# BLDC_Motor.net
KiCad netlist of a schematic drawn in EAGLE
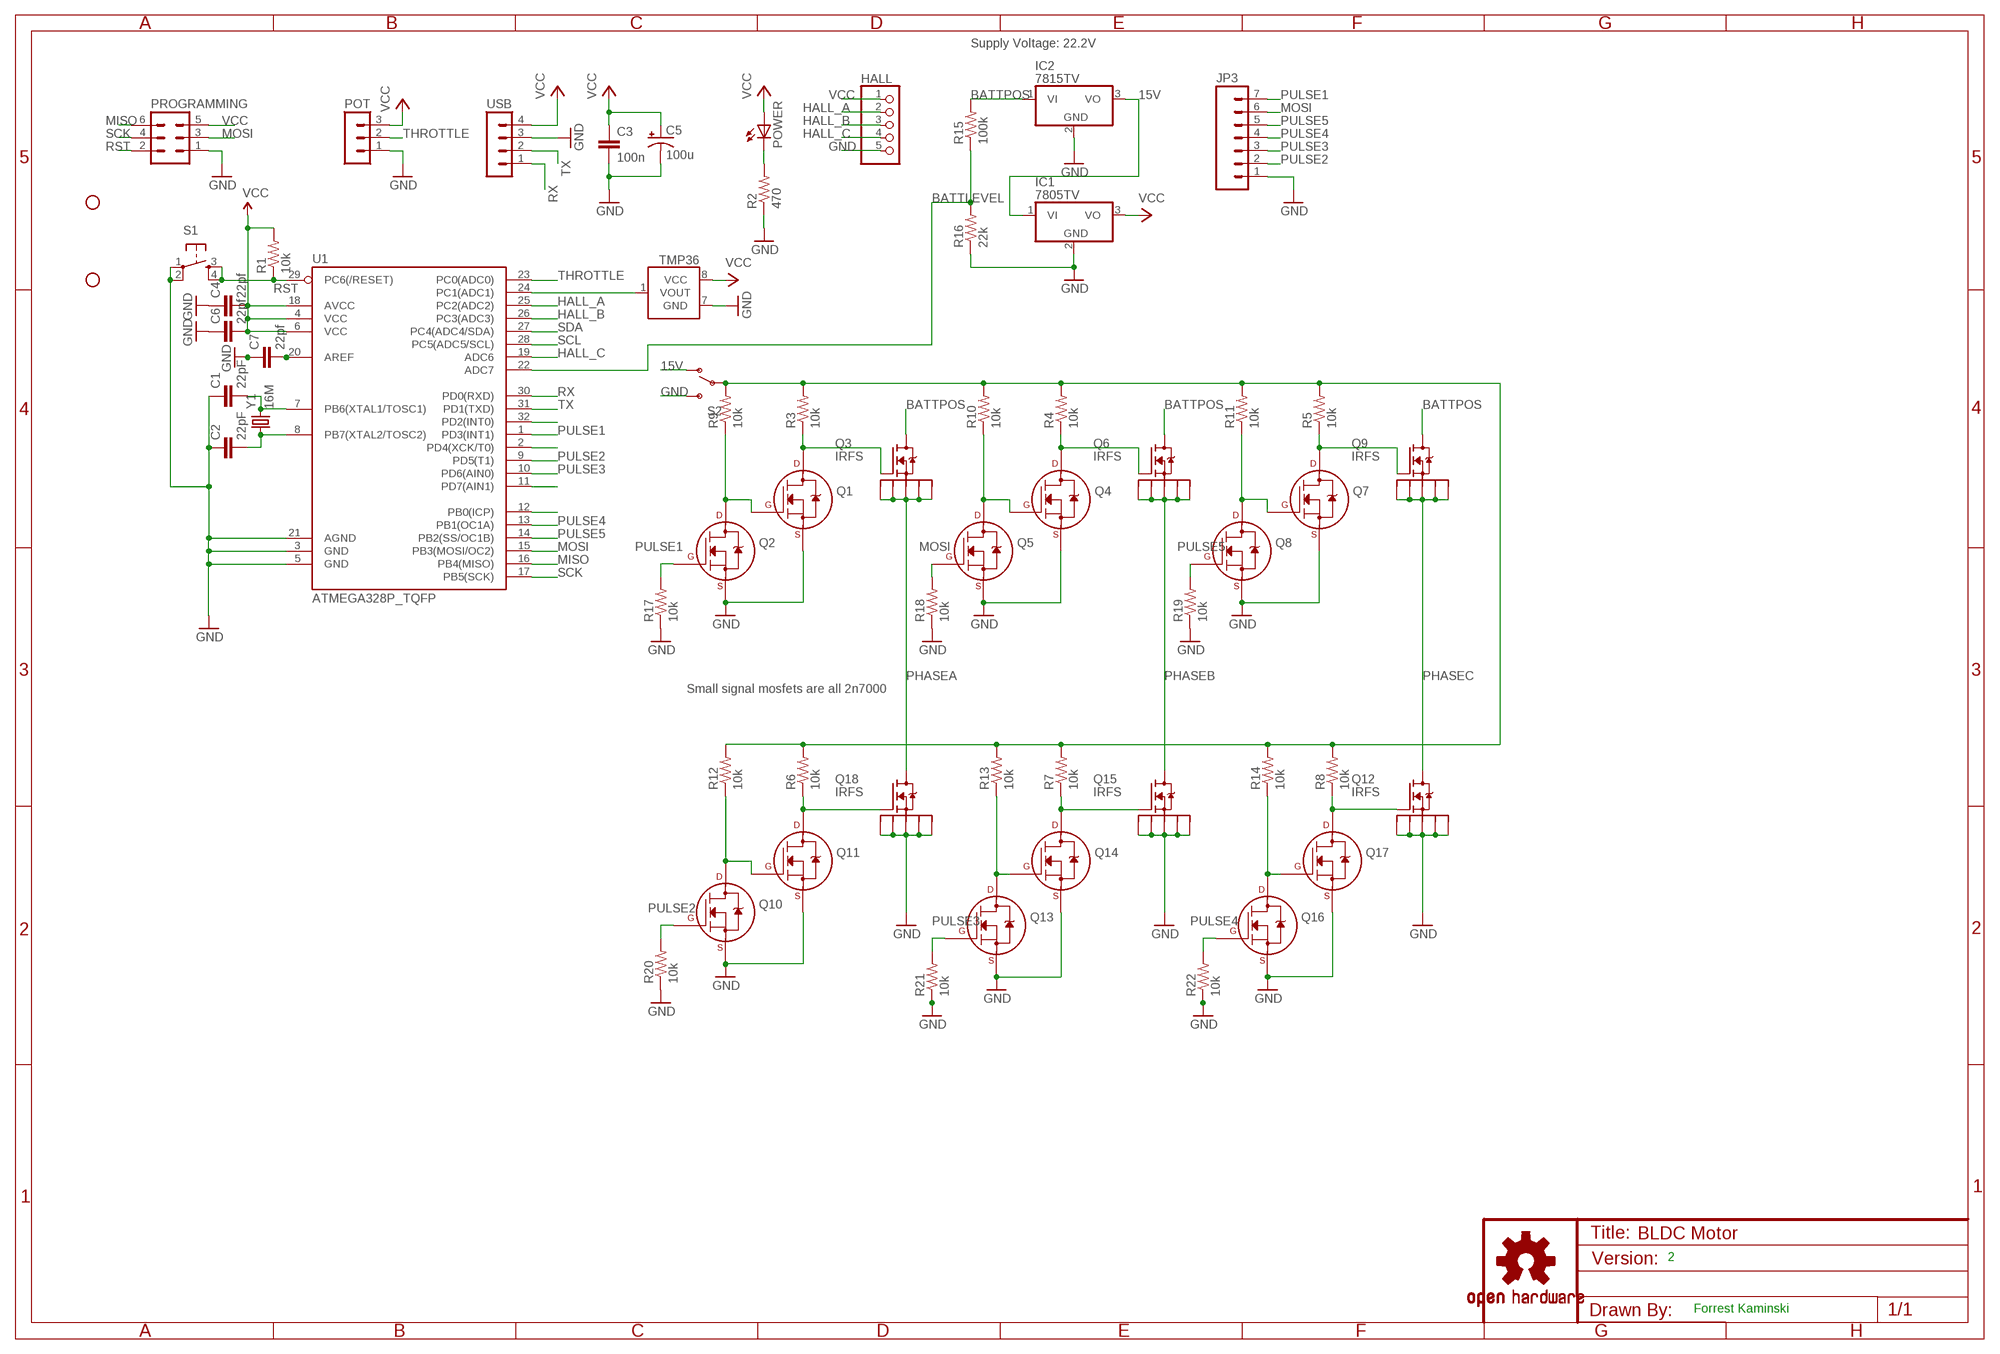
[diagram p0: schematic, sheet 1]

(export (version "E")
  (design (tool "Eeschema 10.0.6"))
  (components
    (comp (ref "C1")
      (value "22pF")
      (footprint "eagle-import:0805")
      (libsource (lib "eagle-import") (part "CAP0805"))
    )
    (comp (ref "C2")
      (value "22pF")
      (footprint "eagle-import:0805")
      (libsource (lib "eagle-import") (part "CAP0805"))
    )
    (comp (ref "C3")
      (value "100n")
      (footprint "eagle-import:0805")
      (libsource (lib "eagle-import") (part "CAP0805"))
    )
    (comp (ref "C4")
      (value "22pf")
      (footprint "eagle-import:0805")
      (libsource (lib "eagle-import") (part "CAP0805"))
    )
    (comp (ref "C5")
      (value "100u")
      (footprint "eagle-import:CPOL-RADIAL-100UF-25V")
      (libsource (lib "eagle-import") (part "CAP_POLPTH1"))
    )
    (comp (ref "C6")
      (value "22pf")
      (footprint "eagle-import:0805")
      (libsource (lib "eagle-import") (part "CAP0805"))
    )
    (comp (ref "C7")
      (value "22pf")
      (footprint "eagle-import:0805")
      (libsource (lib "eagle-import") (part "CAP0805"))
    )
    (comp (ref "HALL")
      (value "PINHD-1X5")
      (footprint "eagle-import:1X05")
      (libsource (lib "eagle-import") (part "PINHD-1X5"))
    )
    (comp (ref "IC1")
      (value "7805TV")
      (footprint "eagle-import:TO220V")
      (libsource (lib "eagle-import") (part "78TV05"))
    )
    (comp (ref "IC2")
      (value "7815TV")
      (footprint "eagle-import:TO220V")
      (libsource (lib "eagle-import") (part "78TV15"))
    )
    (comp (ref "JP1")
      (value "STAND-OFF")
      (footprint "eagle-import:STAND-OFF")
      (libsource (lib "eagle-import") (part "STAND-OFF"))
    )
    (comp (ref "JP2")
      (value "STAND-OFF")
      (footprint "eagle-import:STAND-OFF")
      (libsource (lib "eagle-import") (part "STAND-OFF"))
    )
    (comp (ref "JP3")
      (value "M07")
      (footprint "eagle-import:1X07")
      (libsource (lib "eagle-import") (part "M07"))
    )
    (comp (ref "POT")
      (value "MA03-1")
      (footprint "eagle-import:MA03-1")
      (libsource (lib "eagle-import") (part "MA03-1"))
    )
    (comp (ref "POWER")
      (value "LEDSML0805")
      (footprint "eagle-import:SML0805")
      (libsource (lib "eagle-import") (part "LEDSML0805"))
    )
    (comp (ref "PROGRAMMING")
      (value "MA03-2")
      (footprint "eagle-import:MA03-2")
      (libsource (lib "eagle-import") (part "MA03-2"))
    )
    (comp (ref "Q1")
      (value "2N7000_TO92")
      (footprint "eagle-import:TO-92")
      (libsource (lib "eagle-import") (part "2N700_TO920"))
    )
    (comp (ref "Q2")
      (value "2N7000_TO92")
      (footprint "eagle-import:TO-92")
      (libsource (lib "eagle-import") (part "2N700_TO920"))
    )
    (comp (ref "Q3")
      (value "IRFS")
      (footprint "eagle-import:D2PAK-7")
      (libsource (lib "eagle-import") (part "NMOSFET-D2PAK-7"))
    )
    (comp (ref "Q4")
      (value "2N7000_TO92")
      (footprint "eagle-import:TO-92")
      (libsource (lib "eagle-import") (part "2N700_TO920"))
    )
    (comp (ref "Q5")
      (value "2N7000_TO92")
      (footprint "eagle-import:TO-92")
      (libsource (lib "eagle-import") (part "2N700_TO920"))
    )
    (comp (ref "Q6")
      (value "IRFS")
      (footprint "eagle-import:D2PAK-7")
      (libsource (lib "eagle-import") (part "NMOSFET-D2PAK-7"))
    )
    (comp (ref "Q7")
      (value "2N7000_TO92")
      (footprint "eagle-import:TO-92")
      (libsource (lib "eagle-import") (part "2N700_TO920"))
    )
    (comp (ref "Q8")
      (value "2N7000_TO92")
      (footprint "eagle-import:TO-92")
      (libsource (lib "eagle-import") (part "2N700_TO920"))
    )
    (comp (ref "Q9")
      (value "IRFS")
      (footprint "eagle-import:D2PAK-7")
      (libsource (lib "eagle-import") (part "NMOSFET-D2PAK-7"))
    )
    (comp (ref "Q10")
      (value "2N7000_TO92")
      (footprint "eagle-import:TO-92")
      (libsource (lib "eagle-import") (part "2N700_TO920"))
    )
    (comp (ref "Q11")
      (value "2N7000_TO92")
      (footprint "eagle-import:TO-92")
      (libsource (lib "eagle-import") (part "2N700_TO920"))
    )
    (comp (ref "Q12")
      (value "IRFS")
      (footprint "eagle-import:D2PAK-7")
      (libsource (lib "eagle-import") (part "NMOSFET-D2PAK-7"))
    )
    (comp (ref "Q13")
      (value "2N7000_TO92")
      (footprint "eagle-import:TO-92")
      (libsource (lib "eagle-import") (part "2N700_TO920"))
    )
    (comp (ref "Q14")
      (value "2N7000_TO92")
      (footprint "eagle-import:TO-92")
      (libsource (lib "eagle-import") (part "2N700_TO920"))
    )
    (comp (ref "Q15")
      (value "IRFS")
      (footprint "eagle-import:D2PAK-7")
      (libsource (lib "eagle-import") (part "NMOSFET-D2PAK-7"))
    )
    (comp (ref "Q16")
      (value "2N7000_TO92")
      (footprint "eagle-import:TO-92")
      (libsource (lib "eagle-import") (part "2N700_TO920"))
    )
    (comp (ref "Q17")
      (value "2N7000_TO92")
      (footprint "eagle-import:TO-92")
      (libsource (lib "eagle-import") (part "2N700_TO920"))
    )
    (comp (ref "Q18")
      (value "IRFS")
      (footprint "eagle-import:D2PAK-7")
      (libsource (lib "eagle-import") (part "NMOSFET-D2PAK-7"))
    )
    (comp (ref "R1")
      (value "10k")
      (footprint "eagle-import:0805")
      (libsource (lib "eagle-import") (part "RESISTOR0805-RES"))
    )
    (comp (ref "R2")
      (value "470")
      (footprint "eagle-import:0805")
      (libsource (lib "eagle-import") (part "RESISTOR0805-RES"))
    )
    (comp (ref "R3")
      (value "10k")
      (footprint "eagle-import:0805")
      (libsource (lib "eagle-import") (part "RESISTOR0805-RES"))
    )
    (comp (ref "R4")
      (value "10k")
      (footprint "eagle-import:0805")
      (libsource (lib "eagle-import") (part "RESISTOR0805-RES"))
    )
    (comp (ref "R5")
      (value "10k")
      (footprint "eagle-import:0805")
      (libsource (lib "eagle-import") (part "RESISTOR0805-RES"))
    )
    (comp (ref "R6")
      (value "10k")
      (footprint "eagle-import:0805")
      (libsource (lib "eagle-import") (part "RESISTOR0805-RES"))
    )
    (comp (ref "R7")
      (value "10k")
      (footprint "eagle-import:0805")
      (libsource (lib "eagle-import") (part "RESISTOR0805-RES"))
    )
    (comp (ref "R8")
      (value "10k")
      (footprint "eagle-import:0805")
      (libsource (lib "eagle-import") (part "RESISTOR0805-RES"))
    )
    (comp (ref "R9")
      (value "10k")
      (footprint "eagle-import:0805")
      (libsource (lib "eagle-import") (part "RESISTOR0805-RES"))
    )
    (comp (ref "R10")
      (value "10k")
      (footprint "eagle-import:0805")
      (libsource (lib "eagle-import") (part "RESISTOR0805-RES"))
    )
    (comp (ref "R11")
      (value "10k")
      (footprint "eagle-import:0805")
      (libsource (lib "eagle-import") (part "RESISTOR0805-RES"))
    )
    (comp (ref "R12")
      (value "10k")
      (footprint "eagle-import:0805")
      (libsource (lib "eagle-import") (part "RESISTOR0805-RES"))
    )
    (comp (ref "R13")
      (value "10k")
      (footprint "eagle-import:0805")
      (libsource (lib "eagle-import") (part "RESISTOR0805-RES"))
    )
    (comp (ref "R14")
      (value "10k")
      (footprint "eagle-import:0805")
      (libsource (lib "eagle-import") (part "RESISTOR0805-RES"))
    )
    (comp (ref "R15")
      (value "100k")
      (footprint "eagle-import:0805")
      (libsource (lib "eagle-import") (part "RESISTOR0805-RES"))
    )
    (comp (ref "R16")
      (value "22k")
      (footprint "eagle-import:0805")
      (libsource (lib "eagle-import") (part "RESISTOR0805-RES"))
    )
    (comp (ref "R17")
      (value "10k")
      (footprint "eagle-import:0805")
      (libsource (lib "eagle-import") (part "RESISTOR0805-RES"))
    )
    (comp (ref "R18")
      (value "10k")
      (footprint "eagle-import:0805")
      (libsource (lib "eagle-import") (part "RESISTOR0805-RES"))
    )
    (comp (ref "R19")
      (value "10k")
      (footprint "eagle-import:0805")
      (libsource (lib "eagle-import") (part "RESISTOR0805-RES"))
    )
    (comp (ref "R20")
      (value "10k")
      (footprint "eagle-import:0805")
      (libsource (lib "eagle-import") (part "RESISTOR0805-RES"))
    )
    (comp (ref "R21")
      (value "10k")
      (footprint "eagle-import:0805")
      (libsource (lib "eagle-import") (part "RESISTOR0805-RES"))
    )
    (comp (ref "R22")
      (value "10k")
      (footprint "eagle-import:0805")
      (libsource (lib "eagle-import") (part "RESISTOR0805-RES"))
    )
    (comp (ref "S1")
      (value "TAC_SWITCHPTH")
      (footprint "eagle-import:TACTILE-PTH")
      (libsource (lib "eagle-import") (part "TAC_SWITCHPTH"))
    )
    (comp (ref "S2")
      (value "SWITCH-SPSTPTH_LOCK")
      (footprint "eagle-import:SWITCH-SPDT_LOCK.007S")
      (libsource (lib "eagle-import") (part "SWITCH-SPSTPTH_LOCK"))
    )
    (comp (ref "TMP36")
      (value "TMP36SOIC")
      (footprint "eagle-import:SOIC8")
      (libsource (lib "eagle-import") (part "TMP36SOIC"))
    )
    (comp (ref "U$1")
      (value "OSHW-LOGOS")
      (footprint "eagle-import:OSHW-LOGO-S")
      (libsource (lib "eagle-import") (part "OSHW-LOGOS"))
    )
    (comp (ref "U1")
      (value "ATMEGA328P_TQFP")
      (footprint "eagle-import:TQFP32-08")
      (libsource (lib "eagle-import") (part "ATMEGA328P_TQFP"))
    )
    (comp (ref "USB")
      (value "MA04-1")
      (footprint "eagle-import:MA04-1")
      (libsource (lib "eagle-import") (part "MA04-1"))
    )
    (comp (ref "Y1")
      (value "16M")
      (footprint "eagle-import:HC49US")
      (libsource (lib "eagle-import") (part "CRYSTALHC49US"))
    )
  )
  (nets
    (net (code "1") (name "/15V") (class "Default")
      (node (ref "IC1") (pin "1") (pinfunction "VI_1") (pintype "input"))
      (node (ref "IC2") (pin "3") (pinfunction "VO_3") (pintype "passive"))
      (node (ref "S2") (pin "1") (pinfunction "O_1") (pintype "passive"))
    )
    (net (code "2") (name "/BATTLEVEL") (class "Default")
      (node (ref "R15") (pin "1") (pinfunction "1_1") (pintype "passive"))
      (node (ref "R16") (pin "2") (pinfunction "2_2") (pintype "passive"))
      (node (ref "U1") (pin "22") (pinfunction "ADC7_22") (pintype "bidirectional"))
    )
    (net (code "3") (name "/BATTPOS") (class "Default")
      (node (ref "IC2") (pin "1") (pinfunction "VI_1") (pintype "input"))
      (node (ref "Q3") (pin "D") (pinfunction "D_D") (pintype "passive"))
      (node (ref "Q6") (pin "D") (pinfunction "D_D") (pintype "passive"))
      (node (ref "Q9") (pin "D") (pinfunction "D_D") (pintype "passive"))
      (node (ref "R15") (pin "2") (pinfunction "2_2") (pintype "passive"))
    )
    (net (code "4") (name "/HALL_A") (class "Default")
      (node (ref "HALL") (pin "2") (pinfunction "2_2") (pintype "passive"))
      (node (ref "U1") (pin "25") (pinfunction "PC2(ADC2)_25") (pintype "bidirectional"))
    )
    (net (code "5") (name "/HALL_B") (class "Default")
      (node (ref "HALL") (pin "3") (pinfunction "3_3") (pintype "passive"))
      (node (ref "U1") (pin "26") (pinfunction "PC3(ADC3)_26") (pintype "bidirectional"))
    )
    (net (code "6") (name "/HALL_C") (class "Default")
      (node (ref "HALL") (pin "4") (pinfunction "4_4") (pintype "passive"))
      (node (ref "U1") (pin "19") (pinfunction "ADC6_19") (pintype "bidirectional"))
    )
    (net (code "7") (name "/MISO") (class "Default")
      (node (ref "PROGRAMMING") (pin "6") (pinfunction "6_6") (pintype "passive"))
      (node (ref "U1") (pin "16") (pinfunction "PB4(MISO)_16") (pintype "bidirectional"))
    )
    (net (code "8") (name "/MOSI") (class "Default")
      (node (ref "JP3") (pin "6") (pinfunction "6_6") (pintype "passive"))
      (node (ref "PROGRAMMING") (pin "3") (pinfunction "3_3") (pintype "passive"))
      (node (ref "Q5") (pin "2") (pinfunction "G_2") (pintype "tri_state"))
      (node (ref "R18") (pin "2") (pinfunction "2_2") (pintype "passive"))
      (node (ref "U1") (pin "15") (pinfunction "PB3(MOSI/OC2)_15") (pintype "bidirectional"))
    )
    (net (code "9") (name "/PHASEA") (class "Default")
      (node (ref "Q18") (pin "D") (pinfunction "D_D") (pintype "passive"))
      (node (ref "Q3") (pin "S1") (pinfunction "S1_S1") (pintype "passive"))
      (node (ref "Q3") (pin "S2") (pinfunction "S2_S2") (pintype "passive"))
      (node (ref "Q3") (pin "S3") (pinfunction "S3_S3") (pintype "passive"))
      (node (ref "Q3") (pin "S4") (pinfunction "S4_S4") (pintype "passive"))
      (node (ref "Q3") (pin "S5") (pinfunction "S5_S5") (pintype "passive"))
    )
    (net (code "10") (name "/PHASEB") (class "Default")
      (node (ref "Q15") (pin "D") (pinfunction "D_D") (pintype "passive"))
      (node (ref "Q6") (pin "S1") (pinfunction "S1_S1") (pintype "passive"))
      (node (ref "Q6") (pin "S2") (pinfunction "S2_S2") (pintype "passive"))
      (node (ref "Q6") (pin "S3") (pinfunction "S3_S3") (pintype "passive"))
      (node (ref "Q6") (pin "S4") (pinfunction "S4_S4") (pintype "passive"))
      (node (ref "Q6") (pin "S5") (pinfunction "S5_S5") (pintype "passive"))
    )
    (net (code "11") (name "/PHASEC") (class "Default")
      (node (ref "Q12") (pin "D") (pinfunction "D_D") (pintype "passive"))
      (node (ref "Q9") (pin "S1") (pinfunction "S1_S1") (pintype "passive"))
      (node (ref "Q9") (pin "S2") (pinfunction "S2_S2") (pintype "passive"))
      (node (ref "Q9") (pin "S3") (pinfunction "S3_S3") (pintype "passive"))
      (node (ref "Q9") (pin "S4") (pinfunction "S4_S4") (pintype "passive"))
      (node (ref "Q9") (pin "S5") (pinfunction "S5_S5") (pintype "passive"))
    )
    (net (code "12") (name "/PULSE1") (class "Default")
      (node (ref "JP3") (pin "7") (pinfunction "7_7") (pintype "passive"))
      (node (ref "Q2") (pin "2") (pinfunction "G_2") (pintype "tri_state"))
      (node (ref "R17") (pin "2") (pinfunction "2_2") (pintype "passive"))
      (node (ref "U1") (pin "1") (pinfunction "PD3(INT1)_1") (pintype "bidirectional"))
    )
    (net (code "13") (name "/PULSE2") (class "Default")
      (node (ref "JP3") (pin "2") (pinfunction "2_2") (pintype "passive"))
      (node (ref "Q10") (pin "2") (pinfunction "G_2") (pintype "tri_state"))
      (node (ref "R20") (pin "2") (pinfunction "2_2") (pintype "passive"))
      (node (ref "U1") (pin "9") (pinfunction "PD5(T1)_9") (pintype "bidirectional"))
    )
    (net (code "14") (name "/PULSE3") (class "Default")
      (node (ref "JP3") (pin "3") (pinfunction "3_3") (pintype "passive"))
      (node (ref "Q13") (pin "2") (pinfunction "G_2") (pintype "tri_state"))
      (node (ref "R21") (pin "2") (pinfunction "2_2") (pintype "passive"))
      (node (ref "U1") (pin "10") (pinfunction "PD6(AIN0)_10") (pintype "bidirectional"))
    )
    (net (code "15") (name "/PULSE4") (class "Default")
      (node (ref "JP3") (pin "4") (pinfunction "4_4") (pintype "passive"))
      (node (ref "Q16") (pin "2") (pinfunction "G_2") (pintype "tri_state"))
      (node (ref "R22") (pin "2") (pinfunction "2_2") (pintype "passive"))
      (node (ref "U1") (pin "13") (pinfunction "PB1(OC1A)_13") (pintype "bidirectional"))
    )
    (net (code "16") (name "/PULSE5") (class "Default")
      (node (ref "JP3") (pin "5") (pinfunction "5_5") (pintype "passive"))
      (node (ref "Q8") (pin "2") (pinfunction "G_2") (pintype "tri_state"))
      (node (ref "R19") (pin "2") (pinfunction "2_2") (pintype "passive"))
      (node (ref "U1") (pin "14") (pinfunction "PB2(SS/OC1B)_14") (pintype "bidirectional"))
    )
    (net (code "17") (name "/RST") (class "Default")
      (node (ref "PROGRAMMING") (pin "2") (pinfunction "2_2") (pintype "passive"))
      (node (ref "R1") (pin "1") (pinfunction "1_1") (pintype "passive"))
      (node (ref "S1") (pin "3") (pinfunction "3_3") (pintype "passive"))
      (node (ref "S1") (pin "4") (pinfunction "4_4") (pintype "passive"))
      (node (ref "U1") (pin "29") (pinfunction "PC6(/RESET)_29") (pintype "bidirectional"))
    )
    (net (code "18") (name "/RX") (class "Default")
      (node (ref "U1") (pin "30") (pinfunction "PD0(RXD)_30") (pintype "bidirectional"))
      (node (ref "USB") (pin "1") (pinfunction "1_1") (pintype "passive"))
    )
    (net (code "19") (name "/SCK") (class "Default")
      (node (ref "PROGRAMMING") (pin "4") (pinfunction "4_4") (pintype "passive"))
      (node (ref "U1") (pin "17") (pinfunction "PB5(SCK)_17") (pintype "bidirectional"))
    )
    (net (code "20") (name "/SCL") (class "Default")
      (node (ref "U1") (pin "28") (pinfunction "PC5(ADC5/SCL)_28") (pintype "bidirectional"))
    )
    (net (code "21") (name "/SDA") (class "Default")
      (node (ref "U1") (pin "27") (pinfunction "PC4(ADC4/SDA)_27") (pintype "bidirectional"))
    )
    (net (code "22") (name "/THROTTLE") (class "Default")
      (node (ref "POT") (pin "2") (pinfunction "2_2") (pintype "passive"))
      (node (ref "U1") (pin "23") (pinfunction "PC0(ADC0)_23") (pintype "bidirectional"))
    )
    (net (code "23") (name "/TX") (class "Default")
      (node (ref "U1") (pin "31") (pinfunction "PD1(TXD)_31") (pintype "bidirectional"))
      (node (ref "USB") (pin "2") (pinfunction "2_2") (pintype "passive"))
    )
    (net (code "24") (name "GND") (class "Default")
      (node (ref "C1") (pin "1") (pinfunction "1_1") (pintype "passive"))
      (node (ref "C2") (pin "1") (pinfunction "1_1") (pintype "passive"))
      (node (ref "C3") (pin "2") (pinfunction "2_2") (pintype "passive"))
      (node (ref "C4") (pin "1") (pinfunction "1_1") (pintype "passive"))
      (node (ref "C5") (pin "2") (pinfunction "-_2") (pintype "passive"))
      (node (ref "C6") (pin "1") (pinfunction "1_1") (pintype "passive"))
      (node (ref "C7") (pin "1") (pinfunction "1_1") (pintype "passive"))
      (node (ref "HALL") (pin "5") (pinfunction "5_5") (pintype "passive"))
      (node (ref "IC1") (pin "2") (pinfunction "GND_2") (pintype "passive"))
      (node (ref "IC2") (pin "2") (pinfunction "GND_2") (pintype "passive"))
      (node (ref "JP3") (pin "1") (pinfunction "1_1") (pintype "passive"))
      (node (ref "POT") (pin "1") (pinfunction "1_1") (pintype "passive"))
      (node (ref "PROGRAMMING") (pin "1") (pinfunction "1_1") (pintype "passive"))
      (node (ref "Q1") (pin "1") (pinfunction "S_1") (pintype "bidirectional"))
      (node (ref "Q10") (pin "1") (pinfunction "S_1") (pintype "bidirectional"))
      (node (ref "Q11") (pin "1") (pinfunction "S_1") (pintype "bidirectional"))
      (node (ref "Q12") (pin "S1") (pinfunction "S1_S1") (pintype "passive"))
      (node (ref "Q12") (pin "S2") (pinfunction "S2_S2") (pintype "passive"))
      (node (ref "Q12") (pin "S3") (pinfunction "S3_S3") (pintype "passive"))
      (node (ref "Q12") (pin "S4") (pinfunction "S4_S4") (pintype "passive"))
      (node (ref "Q12") (pin "S5") (pinfunction "S5_S5") (pintype "passive"))
      (node (ref "Q13") (pin "1") (pinfunction "S_1") (pintype "bidirectional"))
      (node (ref "Q14") (pin "1") (pinfunction "S_1") (pintype "bidirectional"))
      (node (ref "Q15") (pin "S1") (pinfunction "S1_S1") (pintype "passive"))
      (node (ref "Q15") (pin "S2") (pinfunction "S2_S2") (pintype "passive"))
      (node (ref "Q15") (pin "S3") (pinfunction "S3_S3") (pintype "passive"))
      (node (ref "Q15") (pin "S4") (pinfunction "S4_S4") (pintype "passive"))
      (node (ref "Q15") (pin "S5") (pinfunction "S5_S5") (pintype "passive"))
      (node (ref "Q16") (pin "1") (pinfunction "S_1") (pintype "bidirectional"))
      (node (ref "Q17") (pin "1") (pinfunction "S_1") (pintype "bidirectional"))
      (node (ref "Q18") (pin "S1") (pinfunction "S1_S1") (pintype "passive"))
      (node (ref "Q18") (pin "S2") (pinfunction "S2_S2") (pintype "passive"))
      (node (ref "Q18") (pin "S3") (pinfunction "S3_S3") (pintype "passive"))
      (node (ref "Q18") (pin "S4") (pinfunction "S4_S4") (pintype "passive"))
      (node (ref "Q18") (pin "S5") (pinfunction "S5_S5") (pintype "passive"))
      (node (ref "Q2") (pin "1") (pinfunction "S_1") (pintype "bidirectional"))
      (node (ref "Q4") (pin "1") (pinfunction "S_1") (pintype "bidirectional"))
      (node (ref "Q5") (pin "1") (pinfunction "S_1") (pintype "bidirectional"))
      (node (ref "Q7") (pin "1") (pinfunction "S_1") (pintype "bidirectional"))
      (node (ref "Q8") (pin "1") (pinfunction "S_1") (pintype "bidirectional"))
      (node (ref "R16") (pin "1") (pinfunction "1_1") (pintype "passive"))
      (node (ref "R17") (pin "1") (pinfunction "1_1") (pintype "passive"))
      (node (ref "R18") (pin "1") (pinfunction "1_1") (pintype "passive"))
      (node (ref "R19") (pin "1") (pinfunction "1_1") (pintype "passive"))
      (node (ref "R2") (pin "1") (pinfunction "1_1") (pintype "passive"))
      (node (ref "R20") (pin "1") (pinfunction "1_1") (pintype "passive"))
      (node (ref "R21") (pin "1") (pinfunction "1_1") (pintype "passive"))
      (node (ref "R22") (pin "1") (pinfunction "1_1") (pintype "passive"))
      (node (ref "S1") (pin "1") (pinfunction "1_1") (pintype "passive"))
      (node (ref "S1") (pin "2") (pinfunction "2_2") (pintype "passive"))
      (node (ref "S2") (pin "3") (pinfunction "S_3") (pintype "passive"))
      (node (ref "TMP36") (pin "7") (pinfunction "GND_7") (pintype "bidirectional"))
      (node (ref "U1") (pin "21") (pinfunction "AGND_21") (pintype "bidirectional"))
      (node (ref "U1") (pin "3") (pinfunction "GND_3") (pintype "bidirectional"))
      (node (ref "U1") (pin "5") (pinfunction "GND_5") (pintype "bidirectional"))
      (node (ref "USB") (pin "3") (pinfunction "3_3") (pintype "passive"))
    )
    (net (code "25") (name "Net-(POWER-PadC)") (class "Default")
      (node (ref "POWER") (pin "C") (pinfunction "C_C") (pintype "passive"))
      (node (ref "R2") (pin "2") (pinfunction "2_2") (pintype "passive"))
    )
    (net (code "26") (name "Net-(Q1-D)") (class "Default")
      (node (ref "Q1") (pin "3") (pinfunction "D_3") (pintype "bidirectional"))
      (node (ref "Q3") (pin "G") (pinfunction "G_G") (pintype "passive"))
      (node (ref "R3") (pin "1") (pinfunction "1_1") (pintype "passive"))
    )
    (net (code "27") (name "Net-(Q1-G)") (class "Default")
      (node (ref "Q1") (pin "2") (pinfunction "G_2") (pintype "tri_state"))
      (node (ref "Q2") (pin "3") (pinfunction "D_3") (pintype "bidirectional"))
      (node (ref "R9") (pin "1") (pinfunction "1_1") (pintype "passive"))
    )
    (net (code "28") (name "Net-(Q4-D)") (class "Default")
      (node (ref "Q4") (pin "3") (pinfunction "D_3") (pintype "bidirectional"))
      (node (ref "Q6") (pin "G") (pinfunction "G_G") (pintype "passive"))
      (node (ref "R4") (pin "1") (pinfunction "1_1") (pintype "passive"))
    )
    (net (code "29") (name "Net-(Q4-G)") (class "Default")
      (node (ref "Q4") (pin "2") (pinfunction "G_2") (pintype "tri_state"))
      (node (ref "Q5") (pin "3") (pinfunction "D_3") (pintype "bidirectional"))
      (node (ref "R10") (pin "1") (pinfunction "1_1") (pintype "passive"))
    )
    (net (code "30") (name "Net-(Q7-D)") (class "Default")
      (node (ref "Q7") (pin "3") (pinfunction "D_3") (pintype "bidirectional"))
      (node (ref "Q9") (pin "G") (pinfunction "G_G") (pintype "passive"))
      (node (ref "R5") (pin "1") (pinfunction "1_1") (pintype "passive"))
    )
    (net (code "31") (name "Net-(Q7-G)") (class "Default")
      (node (ref "Q7") (pin "2") (pinfunction "G_2") (pintype "tri_state"))
      (node (ref "Q8") (pin "3") (pinfunction "D_3") (pintype "bidirectional"))
      (node (ref "R11") (pin "1") (pinfunction "1_1") (pintype "passive"))
    )
    (net (code "32") (name "Net-(Q10-D)") (class "Default")
      (node (ref "Q10") (pin "3") (pinfunction "D_3") (pintype "bidirectional"))
      (node (ref "Q11") (pin "2") (pinfunction "G_2") (pintype "tri_state"))
      (node (ref "R12") (pin "1") (pinfunction "1_1") (pintype "passive"))
    )
    (net (code "33") (name "Net-(Q11-D)") (class "Default")
      (node (ref "Q11") (pin "3") (pinfunction "D_3") (pintype "bidirectional"))
      (node (ref "Q18") (pin "G") (pinfunction "G_G") (pintype "passive"))
      (node (ref "R6") (pin "1") (pinfunction "1_1") (pintype "passive"))
    )
    (net (code "34") (name "Net-(Q13-D)") (class "Default")
      (node (ref "Q13") (pin "3") (pinfunction "D_3") (pintype "bidirectional"))
      (node (ref "Q14") (pin "2") (pinfunction "G_2") (pintype "tri_state"))
      (node (ref "R13") (pin "1") (pinfunction "1_1") (pintype "passive"))
    )
    (net (code "35") (name "Net-(Q14-D)") (class "Default")
      (node (ref "Q14") (pin "3") (pinfunction "D_3") (pintype "bidirectional"))
      (node (ref "Q15") (pin "G") (pinfunction "G_G") (pintype "passive"))
      (node (ref "R7") (pin "1") (pinfunction "1_1") (pintype "passive"))
    )
    (net (code "36") (name "Net-(Q16-D)") (class "Default")
      (node (ref "Q16") (pin "3") (pinfunction "D_3") (pintype "bidirectional"))
      (node (ref "Q17") (pin "2") (pinfunction "G_2") (pintype "tri_state"))
      (node (ref "R14") (pin "1") (pinfunction "1_1") (pintype "passive"))
    )
    (net (code "37") (name "Net-(Q17-D)") (class "Default")
      (node (ref "Q12") (pin "G") (pinfunction "G_G") (pintype "passive"))
      (node (ref "Q17") (pin "3") (pinfunction "D_3") (pintype "bidirectional"))
      (node (ref "R8") (pin "1") (pinfunction "1_1") (pintype "passive"))
    )
    (net (code "38") (name "Net-(S2-P)") (class "Default")
      (node (ref "R10") (pin "2") (pinfunction "2_2") (pintype "passive"))
      (node (ref "R11") (pin "2") (pinfunction "2_2") (pintype "passive"))
      (node (ref "R12") (pin "2") (pinfunction "2_2") (pintype "passive"))
      (node (ref "R13") (pin "2") (pinfunction "2_2") (pintype "passive"))
      (node (ref "R14") (pin "2") (pinfunction "2_2") (pintype "passive"))
      (node (ref "R3") (pin "2") (pinfunction "2_2") (pintype "passive"))
      (node (ref "R4") (pin "2") (pinfunction "2_2") (pintype "passive"))
      (node (ref "R5") (pin "2") (pinfunction "2_2") (pintype "passive"))
      (node (ref "R6") (pin "2") (pinfunction "2_2") (pintype "passive"))
      (node (ref "R7") (pin "2") (pinfunction "2_2") (pintype "passive"))
      (node (ref "R8") (pin "2") (pinfunction "2_2") (pintype "passive"))
      (node (ref "R9") (pin "2") (pinfunction "2_2") (pintype "passive"))
      (node (ref "S2") (pin "2") (pinfunction "P_2") (pintype "passive"))
    )
    (net (code "39") (name "Net-(TMP36-VOUT)") (class "Default")
      (node (ref "TMP36") (pin "1") (pinfunction "VOUT_1") (pintype "bidirectional"))
      (node (ref "U1") (pin "24") (pinfunction "PC1(ADC1)_24") (pintype "bidirectional"))
    )
    (net (code "40") (name "Net-(U1-AREF)") (class "Default")
      (node (ref "C7") (pin "2") (pinfunction "2_2") (pintype "passive"))
      (node (ref "U1") (pin "20") (pinfunction "AREF_20") (pintype "bidirectional"))
    )
    (net (code "41") (name "Net-(U1-PB6(XTAL1{slash}TOSC1))") (class "Default")
      (node (ref "C1") (pin "2") (pinfunction "2_2") (pintype "passive"))
      (node (ref "U1") (pin "7") (pinfunction "PB6(XTAL1/TOSC1)_7") (pintype "bidirectional"))
      (node (ref "Y1") (pin "2") (pinfunction "2_2") (pintype "passive"))
    )
    (net (code "42") (name "Net-(U1-PB7(XTAL2{slash}TOSC2))") (class "Default")
      (node (ref "C2") (pin "2") (pinfunction "2_2") (pintype "passive"))
      (node (ref "U1") (pin "8") (pinfunction "PB7(XTAL2/TOSC2)_8") (pintype "bidirectional"))
      (node (ref "Y1") (pin "1") (pinfunction "1_1") (pintype "passive"))
    )
    (net (code "43") (name "VCC") (class "Default")
      (node (ref "C3") (pin "1") (pinfunction "1_1") (pintype "passive"))
      (node (ref "C4") (pin "2") (pinfunction "2_2") (pintype "passive"))
      (node (ref "C5") (pin "1") (pinfunction "+_1") (pintype "passive"))
      (node (ref "C6") (pin "2") (pinfunction "2_2") (pintype "passive"))
      (node (ref "HALL") (pin "1") (pinfunction "1_1") (pintype "passive"))
      (node (ref "IC1") (pin "3") (pinfunction "VO_3") (pintype "passive"))
      (node (ref "POT") (pin "3") (pinfunction "3_3") (pintype "passive"))
      (node (ref "POWER") (pin "A") (pinfunction "A_A") (pintype "passive"))
      (node (ref "PROGRAMMING") (pin "5") (pinfunction "5_5") (pintype "passive"))
      (node (ref "R1") (pin "2") (pinfunction "2_2") (pintype "passive"))
      (node (ref "TMP36") (pin "8") (pinfunction "VCC_8") (pintype "bidirectional"))
      (node (ref "U1") (pin "18") (pinfunction "AVCC_18") (pintype "bidirectional"))
      (node (ref "U1") (pin "4") (pinfunction "VCC_4") (pintype "bidirectional"))
      (node (ref "U1") (pin "6") (pinfunction "VCC_6") (pintype "bidirectional"))
      (node (ref "USB") (pin "4") (pinfunction "4_4") (pintype "passive"))
    )
    (net (code "44") (name "unconnected-(U1-PB0(ICP)-Pad12)") (class "Default")
      (node (ref "U1") (pin "12") (pinfunction "PB0(ICP)_12") (pintype "bidirectional"))
    )
    (net (code "45") (name "unconnected-(U1-PD2(INT0)-Pad32)") (class "Default")
      (node (ref "U1") (pin "32") (pinfunction "PD2(INT0)_32") (pintype "bidirectional"))
    )
    (net (code "46") (name "unconnected-(U1-PD4(XCK{slash}T0)-Pad2)") (class "Default")
      (node (ref "U1") (pin "2") (pinfunction "PD4(XCK/T0)_2") (pintype "bidirectional"))
    )
    (net (code "47") (name "unconnected-(U1-PD7(AIN1)-Pad11)") (class "Default")
      (node (ref "U1") (pin "11") (pinfunction "PD7(AIN1)_11") (pintype "bidirectional"))
    )
  )
)
